# analog.net
KiCad netlist of a schematic drawn in EAGLE
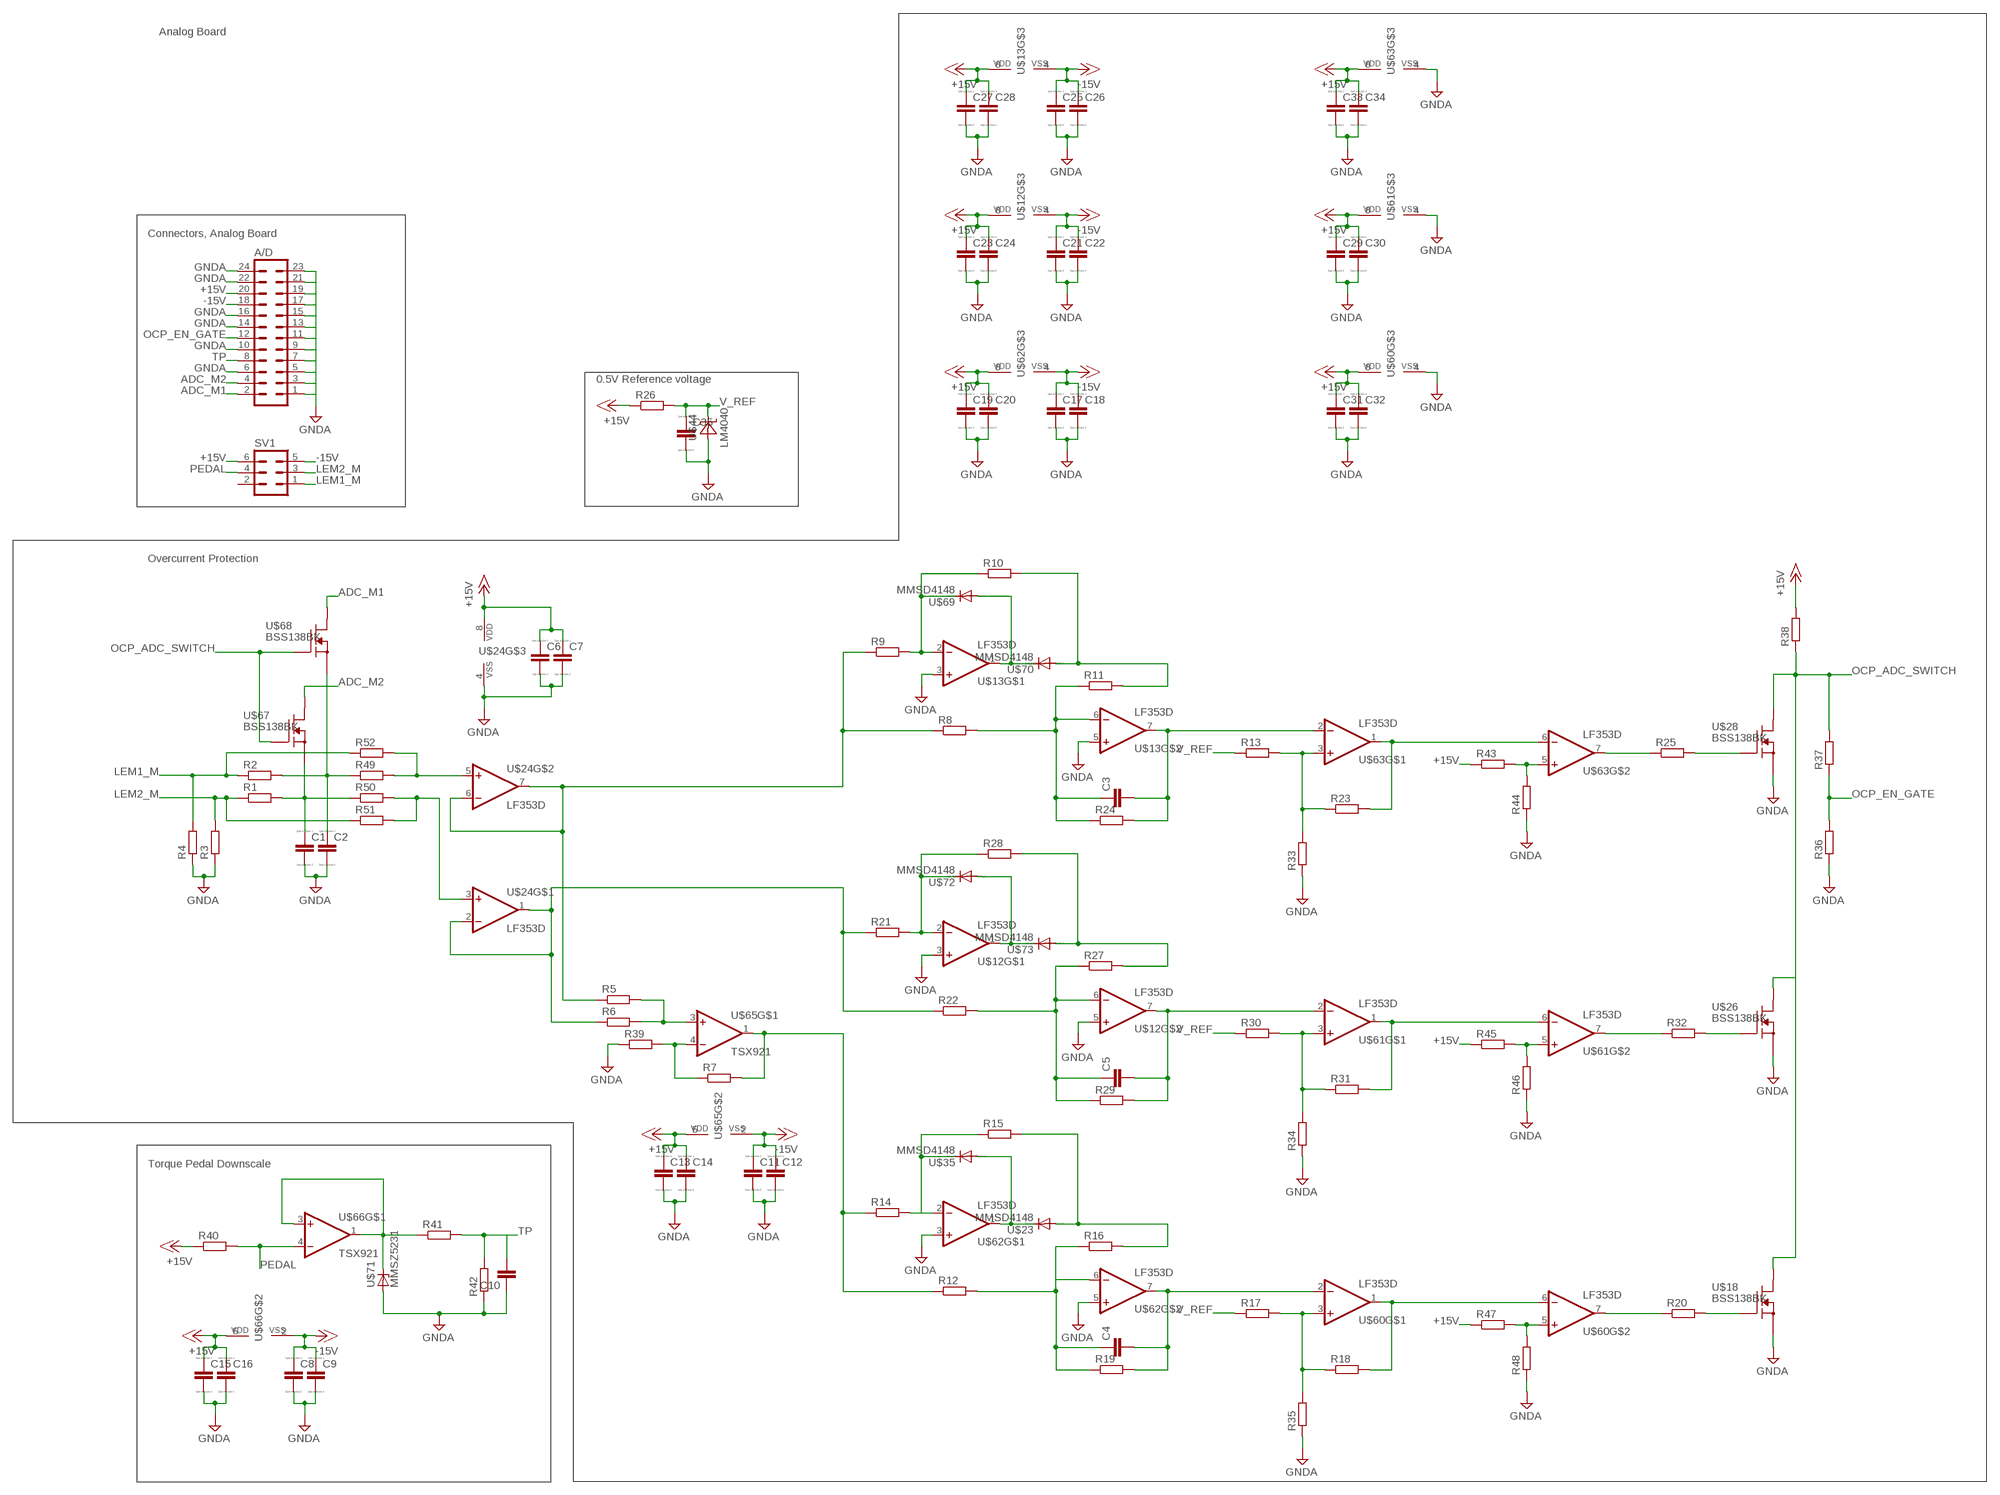
[diagram p0: schematic, sheet 1]

(export (version "E")
  (design (tool "Eeschema 10.0.6"))
  (components
    (comp (ref "A/D")
      (value "MA12-2")
      (footprint "eagle-import:MA12-2")
      (libsource (lib "eagle-import") (part "MA12-2"))
    )
    (comp (ref "C1")
      (value "CC1206")
      (footprint "eagle-import:C1206")
      (libsource (lib "eagle-import") (part "CC1206"))
    )
    (comp (ref "C2")
      (value "CC1206")
      (footprint "eagle-import:C1206")
      (libsource (lib "eagle-import") (part "CC1206"))
    )
    (comp (ref "C3")
      (value "C-EUC0805")
      (footprint "eagle-import:C0805")
      (libsource (lib "eagle-import") (part "C-EUC0805"))
    )
    (comp (ref "C4")
      (value "C-EUC0805")
      (footprint "eagle-import:C0805")
      (libsource (lib "eagle-import") (part "C-EUC0805"))
    )
    (comp (ref "C5")
      (value "C-EUC0805")
      (footprint "eagle-import:C0805")
      (libsource (lib "eagle-import") (part "C-EUC0805"))
    )
    (comp (ref "C6")
      (value "CC1206")
      (footprint "eagle-import:C1206")
      (libsource (lib "eagle-import") (part "CC1206"))
    )
    (comp (ref "C7")
      (value "CC1206")
      (footprint "eagle-import:C1206")
      (libsource (lib "eagle-import") (part "CC1206"))
    )
    (comp (ref "C8")
      (value "CC1206")
      (footprint "eagle-import:C1206")
      (libsource (lib "eagle-import") (part "CC1206"))
    )
    (comp (ref "C9")
      (value "CC1206")
      (footprint "eagle-import:C1206")
      (libsource (lib "eagle-import") (part "CC1206"))
    )
    (comp (ref "C10")
      (value "C-EUC0805")
      (footprint "eagle-import:C0805")
      (libsource (lib "eagle-import") (part "C-EUC0805"))
    )
    (comp (ref "C11")
      (value "CC1206")
      (footprint "eagle-import:C1206")
      (libsource (lib "eagle-import") (part "CC1206"))
    )
    (comp (ref "C12")
      (value "CC1206")
      (footprint "eagle-import:C1206")
      (libsource (lib "eagle-import") (part "CC1206"))
    )
    (comp (ref "C13")
      (value "CC1206")
      (footprint "eagle-import:C1206")
      (libsource (lib "eagle-import") (part "CC1206"))
    )
    (comp (ref "C14")
      (value "CC1206")
      (footprint "eagle-import:C1206")
      (libsource (lib "eagle-import") (part "CC1206"))
    )
    (comp (ref "C15")
      (value "CC1206")
      (footprint "eagle-import:C1206")
      (libsource (lib "eagle-import") (part "CC1206"))
    )
    (comp (ref "C16")
      (value "CC1206")
      (footprint "eagle-import:C1206")
      (libsource (lib "eagle-import") (part "CC1206"))
    )
    (comp (ref "C17")
      (value "CC1206")
      (footprint "eagle-import:C1206")
      (libsource (lib "eagle-import") (part "CC1206"))
    )
    (comp (ref "C18")
      (value "CC1206")
      (footprint "eagle-import:C1206")
      (libsource (lib "eagle-import") (part "CC1206"))
    )
    (comp (ref "C19")
      (value "CC1206")
      (footprint "eagle-import:C1206")
      (libsource (lib "eagle-import") (part "CC1206"))
    )
    (comp (ref "C20")
      (value "CC1206")
      (footprint "eagle-import:C1206")
      (libsource (lib "eagle-import") (part "CC1206"))
    )
    (comp (ref "C21")
      (value "CC1206")
      (footprint "eagle-import:C1206")
      (libsource (lib "eagle-import") (part "CC1206"))
    )
    (comp (ref "C22")
      (value "CC1206")
      (footprint "eagle-import:C1206")
      (libsource (lib "eagle-import") (part "CC1206"))
    )
    (comp (ref "C23")
      (value "CC1206")
      (footprint "eagle-import:C1206")
      (libsource (lib "eagle-import") (part "CC1206"))
    )
    (comp (ref "C24")
      (value "CC1206")
      (footprint "eagle-import:C1206")
      (libsource (lib "eagle-import") (part "CC1206"))
    )
    (comp (ref "C25")
      (value "CC1206")
      (footprint "eagle-import:C1206")
      (libsource (lib "eagle-import") (part "CC1206"))
    )
    (comp (ref "C26")
      (value "CC1206")
      (footprint "eagle-import:C1206")
      (libsource (lib "eagle-import") (part "CC1206"))
    )
    (comp (ref "C27")
      (value "CC1206")
      (footprint "eagle-import:C1206")
      (libsource (lib "eagle-import") (part "CC1206"))
    )
    (comp (ref "C28")
      (value "CC1206")
      (footprint "eagle-import:C1206")
      (libsource (lib "eagle-import") (part "CC1206"))
    )
    (comp (ref "C29")
      (value "CC1206")
      (footprint "eagle-import:C1206")
      (libsource (lib "eagle-import") (part "CC1206"))
    )
    (comp (ref "C30")
      (value "CC1206")
      (footprint "eagle-import:C1206")
      (libsource (lib "eagle-import") (part "CC1206"))
    )
    (comp (ref "C31")
      (value "CC1206")
      (footprint "eagle-import:C1206")
      (libsource (lib "eagle-import") (part "CC1206"))
    )
    (comp (ref "C32")
      (value "CC1206")
      (footprint "eagle-import:C1206")
      (libsource (lib "eagle-import") (part "CC1206"))
    )
    (comp (ref "C33")
      (value "CC1206")
      (footprint "eagle-import:C1206")
      (libsource (lib "eagle-import") (part "CC1206"))
    )
    (comp (ref "C34")
      (value "CC1206")
      (footprint "eagle-import:C1206")
      (libsource (lib "eagle-import") (part "CC1206"))
    )
    (comp (ref "C35")
      (value "CC1206")
      (footprint "eagle-import:C1206")
      (libsource (lib "eagle-import") (part "CC1206"))
    )
    (comp (ref "R1")
      (value "R-EU_M0805")
      (footprint "eagle-import:M0805")
      (libsource (lib "eagle-import") (part "R-EU_M0805"))
    )
    (comp (ref "R2")
      (value "R-EU_M0805")
      (footprint "eagle-import:M0805")
      (libsource (lib "eagle-import") (part "R-EU_M0805"))
    )
    (comp (ref "R3")
      (value "R-EU_M0805")
      (footprint "eagle-import:M0805")
      (libsource (lib "eagle-import") (part "R-EU_M0805"))
    )
    (comp (ref "R4")
      (value "R-EU_M0805")
      (footprint "eagle-import:M0805")
      (libsource (lib "eagle-import") (part "R-EU_M0805"))
    )
    (comp (ref "R5")
      (value "R-EU_M0805")
      (footprint "eagle-import:M0805")
      (libsource (lib "eagle-import") (part "R-EU_M0805"))
    )
    (comp (ref "R6")
      (value "R-EU_M0805")
      (footprint "eagle-import:M0805")
      (libsource (lib "eagle-import") (part "R-EU_M0805"))
    )
    (comp (ref "R7")
      (value "R-EU_M0805")
      (footprint "eagle-import:M0805")
      (libsource (lib "eagle-import") (part "R-EU_M0805"))
    )
    (comp (ref "R8")
      (value "R-EU_M0805")
      (footprint "eagle-import:M0805")
      (libsource (lib "eagle-import") (part "R-EU_M0805"))
    )
    (comp (ref "R9")
      (value "R-EU_M0805")
      (footprint "eagle-import:M0805")
      (libsource (lib "eagle-import") (part "R-EU_M0805"))
    )
    (comp (ref "R10")
      (value "R-EU_M0805")
      (footprint "eagle-import:M0805")
      (libsource (lib "eagle-import") (part "R-EU_M0805"))
    )
    (comp (ref "R11")
      (value "R-EU_M0805")
      (footprint "eagle-import:M0805")
      (libsource (lib "eagle-import") (part "R-EU_M0805"))
    )
    (comp (ref "R12")
      (value "R-EU_M0805")
      (footprint "eagle-import:M0805")
      (libsource (lib "eagle-import") (part "R-EU_M0805"))
    )
    (comp (ref "R13")
      (value "R-EU_M0805")
      (footprint "eagle-import:M0805")
      (libsource (lib "eagle-import") (part "R-EU_M0805"))
    )
    (comp (ref "R14")
      (value "R-EU_M0805")
      (footprint "eagle-import:M0805")
      (libsource (lib "eagle-import") (part "R-EU_M0805"))
    )
    (comp (ref "R15")
      (value "R-EU_M0805")
      (footprint "eagle-import:M0805")
      (libsource (lib "eagle-import") (part "R-EU_M0805"))
    )
    (comp (ref "R16")
      (value "R-EU_M0805")
      (footprint "eagle-import:M0805")
      (libsource (lib "eagle-import") (part "R-EU_M0805"))
    )
    (comp (ref "R17")
      (value "R-EU_M0805")
      (footprint "eagle-import:M0805")
      (libsource (lib "eagle-import") (part "R-EU_M0805"))
    )
    (comp (ref "R18")
      (value "R-EU_M0805")
      (footprint "eagle-import:M0805")
      (libsource (lib "eagle-import") (part "R-EU_M0805"))
    )
    (comp (ref "R19")
      (value "R-EU_M0805")
      (footprint "eagle-import:M0805")
      (libsource (lib "eagle-import") (part "R-EU_M0805"))
    )
    (comp (ref "R20")
      (value "R-EU_M0805")
      (footprint "eagle-import:M0805")
      (libsource (lib "eagle-import") (part "R-EU_M0805"))
    )
    (comp (ref "R21")
      (value "R-EU_M0805")
      (footprint "eagle-import:M0805")
      (libsource (lib "eagle-import") (part "R-EU_M0805"))
    )
    (comp (ref "R22")
      (value "R-EU_M0805")
      (footprint "eagle-import:M0805")
      (libsource (lib "eagle-import") (part "R-EU_M0805"))
    )
    (comp (ref "R23")
      (value "R-EU_M0805")
      (footprint "eagle-import:M0805")
      (libsource (lib "eagle-import") (part "R-EU_M0805"))
    )
    (comp (ref "R24")
      (value "R-EU_M0805")
      (footprint "eagle-import:M0805")
      (libsource (lib "eagle-import") (part "R-EU_M0805"))
    )
    (comp (ref "R25")
      (value "R-EU_M0805")
      (footprint "eagle-import:M0805")
      (libsource (lib "eagle-import") (part "R-EU_M0805"))
    )
    (comp (ref "R26")
      (value "R-EU_M0805")
      (footprint "eagle-import:M0805")
      (libsource (lib "eagle-import") (part "R-EU_M0805"))
    )
    (comp (ref "R27")
      (value "R-EU_M0805")
      (footprint "eagle-import:M0805")
      (libsource (lib "eagle-import") (part "R-EU_M0805"))
    )
    (comp (ref "R28")
      (value "R-EU_M0805")
      (footprint "eagle-import:M0805")
      (libsource (lib "eagle-import") (part "R-EU_M0805"))
    )
    (comp (ref "R29")
      (value "R-EU_M0805")
      (footprint "eagle-import:M0805")
      (libsource (lib "eagle-import") (part "R-EU_M0805"))
    )
    (comp (ref "R30")
      (value "R-EU_M0805")
      (footprint "eagle-import:M0805")
      (libsource (lib "eagle-import") (part "R-EU_M0805"))
    )
    (comp (ref "R31")
      (value "R-EU_M0805")
      (footprint "eagle-import:M0805")
      (libsource (lib "eagle-import") (part "R-EU_M0805"))
    )
    (comp (ref "R32")
      (value "R-EU_M0805")
      (footprint "eagle-import:M0805")
      (libsource (lib "eagle-import") (part "R-EU_M0805"))
    )
    (comp (ref "R33")
      (value "R-EU_M0805")
      (footprint "eagle-import:M0805")
      (libsource (lib "eagle-import") (part "R-EU_M0805"))
    )
    (comp (ref "R34")
      (value "R-EU_M0805")
      (footprint "eagle-import:M0805")
      (libsource (lib "eagle-import") (part "R-EU_M0805"))
    )
    (comp (ref "R35")
      (value "R-EU_M0805")
      (footprint "eagle-import:M0805")
      (libsource (lib "eagle-import") (part "R-EU_M0805"))
    )
    (comp (ref "R36")
      (value "R-EU_M0805")
      (footprint "eagle-import:M0805")
      (libsource (lib "eagle-import") (part "R-EU_M0805"))
    )
    (comp (ref "R37")
      (value "R-EU_M0805")
      (footprint "eagle-import:M0805")
      (libsource (lib "eagle-import") (part "R-EU_M0805"))
    )
    (comp (ref "R38")
      (value "R-EU_M0805")
      (footprint "eagle-import:M0805")
      (libsource (lib "eagle-import") (part "R-EU_M0805"))
    )
    (comp (ref "R39")
      (value "R-EU_M0805")
      (footprint "eagle-import:M0805")
      (libsource (lib "eagle-import") (part "R-EU_M0805"))
    )
    (comp (ref "R40")
      (value "R-EU_M0805")
      (footprint "eagle-import:M0805")
      (libsource (lib "eagle-import") (part "R-EU_M0805"))
    )
    (comp (ref "R41")
      (value "R-EU_M0805")
      (footprint "eagle-import:M0805")
      (libsource (lib "eagle-import") (part "R-EU_M0805"))
    )
    (comp (ref "R42")
      (value "R-EU_M0805")
      (footprint "eagle-import:M0805")
      (libsource (lib "eagle-import") (part "R-EU_M0805"))
    )
    (comp (ref "R43")
      (value "R-EU_M0805")
      (footprint "eagle-import:M0805")
      (libsource (lib "eagle-import") (part "R-EU_M0805"))
    )
    (comp (ref "R44")
      (value "R-EU_M0805")
      (footprint "eagle-import:M0805")
      (libsource (lib "eagle-import") (part "R-EU_M0805"))
    )
    (comp (ref "R45")
      (value "R-EU_M0805")
      (footprint "eagle-import:M0805")
      (libsource (lib "eagle-import") (part "R-EU_M0805"))
    )
    (comp (ref "R46")
      (value "R-EU_M0805")
      (footprint "eagle-import:M0805")
      (libsource (lib "eagle-import") (part "R-EU_M0805"))
    )
    (comp (ref "R47")
      (value "R-EU_M0805")
      (footprint "eagle-import:M0805")
      (libsource (lib "eagle-import") (part "R-EU_M0805"))
    )
    (comp (ref "R48")
      (value "R-EU_M0805")
      (footprint "eagle-import:M0805")
      (libsource (lib "eagle-import") (part "R-EU_M0805"))
    )
    (comp (ref "R49")
      (value "R-EU_M0805")
      (footprint "eagle-import:M0805")
      (libsource (lib "eagle-import") (part "R-EU_M0805"))
    )
    (comp (ref "R50")
      (value "R-EU_M0805")
      (footprint "eagle-import:M0805")
      (libsource (lib "eagle-import") (part "R-EU_M0805"))
    )
    (comp (ref "R51")
      (value "R-EU_M0805")
      (footprint "eagle-import:M0805")
      (libsource (lib "eagle-import") (part "R-EU_M0805"))
    )
    (comp (ref "R52")
      (value "R-EU_M0805")
      (footprint "eagle-import:M0805")
      (libsource (lib "eagle-import") (part "R-EU_M0805"))
    )
    (comp (ref "SV1")
      (value "MA03-2")
      (footprint "eagle-import:MA03-2")
      (libsource (lib "eagle-import") (part "MA03-2"))
    )
    (comp (ref "U$12")
      (value "LF353D")
      (footprint "eagle-import:SO08")
      (libsource (lib "eagle-import") (part "LF353D"))
    )
    (comp (ref "U$13")
      (value "LF353D")
      (footprint "eagle-import:SO08")
      (libsource (lib "eagle-import") (part "LF353D"))
    )
    (comp (ref "U$18")
      (value "BSS138BK")
      (footprint "eagle-import:SOT23")
      (libsource (lib "eagle-import") (part "BSS138BK"))
    )
    (comp (ref "U$23")
      (value "MMSD4148")
      (footprint "eagle-import:SOD123")
      (libsource (lib "eagle-import") (part "MMSD4148"))
    )
    (comp (ref "U$24")
      (value "LF353D")
      (footprint "eagle-import:SO08")
      (libsource (lib "eagle-import") (part "LF353D"))
    )
    (comp (ref "U$26")
      (value "BSS138BK")
      (footprint "eagle-import:SOT23")
      (libsource (lib "eagle-import") (part "BSS138BK"))
    )
    (comp (ref "U$28")
      (value "BSS138BK")
      (footprint "eagle-import:SOT23")
      (libsource (lib "eagle-import") (part "BSS138BK"))
    )
    (comp (ref "U$35")
      (value "MMSD4148")
      (footprint "eagle-import:SOD123")
      (libsource (lib "eagle-import") (part "MMSD4148"))
    )
    (comp (ref "U$44")
      (value "LM4040")
      (footprint "eagle-import:SOT23")
      (libsource (lib "eagle-import") (part "LM4040"))
    )
    (comp (ref "U$60")
      (value "LF353D")
      (footprint "eagle-import:SO08")
      (libsource (lib "eagle-import") (part "LF353D"))
    )
    (comp (ref "U$61")
      (value "LF353D")
      (footprint "eagle-import:SO08")
      (libsource (lib "eagle-import") (part "LF353D"))
    )
    (comp (ref "U$62")
      (value "LF353D")
      (footprint "eagle-import:SO08")
      (libsource (lib "eagle-import") (part "LF353D"))
    )
    (comp (ref "U$63")
      (value "LF353D")
      (footprint "eagle-import:SO08")
      (libsource (lib "eagle-import") (part "LF353D"))
    )
    (comp (ref "U$65")
      (value "TSX921")
      (footprint "eagle-import:SOT23-5")
      (libsource (lib "eagle-import") (part "TSX921"))
    )
    (comp (ref "U$66")
      (value "TSX921")
      (footprint "eagle-import:SOT23-5")
      (libsource (lib "eagle-import") (part "TSX921"))
    )
    (comp (ref "U$67")
      (value "BSS138BK")
      (footprint "eagle-import:SOT23")
      (libsource (lib "eagle-import") (part "BSS138BK"))
    )
    (comp (ref "U$68")
      (value "BSS138BK")
      (footprint "eagle-import:SOT23")
      (libsource (lib "eagle-import") (part "BSS138BK"))
    )
    (comp (ref "U$69")
      (value "MMSD4148")
      (footprint "eagle-import:SOD123")
      (libsource (lib "eagle-import") (part "MMSD4148"))
    )
    (comp (ref "U$70")
      (value "MMSD4148")
      (footprint "eagle-import:SOD123")
      (libsource (lib "eagle-import") (part "MMSD4148"))
    )
    (comp (ref "U$71")
      (value "MMSZ5231")
      (footprint "eagle-import:SOD123")
      (libsource (lib "eagle-import") (part "MMSZ5231"))
    )
    (comp (ref "U$72")
      (value "MMSD4148")
      (footprint "eagle-import:SOD123")
      (libsource (lib "eagle-import") (part "MMSD4148"))
    )
    (comp (ref "U$73")
      (value "MMSD4148")
      (footprint "eagle-import:SOD123")
      (libsource (lib "eagle-import") (part "MMSD4148"))
    )
  )
  (nets
    (net (code "1") (name "+15V") (class "Default")
      (node (ref "A/D") (pin "20") (pinfunction "20_20") (pintype "passive"))
      (node (ref "C13") (pin "1") (pinfunction "1_1") (pintype "passive"))
      (node (ref "C14") (pin "1") (pinfunction "1_1") (pintype "passive"))
      (node (ref "C15") (pin "1") (pinfunction "1_1") (pintype "passive"))
      (node (ref "C16") (pin "1") (pinfunction "1_1") (pintype "passive"))
      (node (ref "C19") (pin "1") (pinfunction "1_1") (pintype "passive"))
      (node (ref "C20") (pin "1") (pinfunction "1_1") (pintype "passive"))
      (node (ref "C23") (pin "1") (pinfunction "1_1") (pintype "passive"))
      (node (ref "C24") (pin "1") (pinfunction "1_1") (pintype "passive"))
      (node (ref "C27") (pin "1") (pinfunction "1_1") (pintype "passive"))
      (node (ref "C28") (pin "1") (pinfunction "1_1") (pintype "passive"))
      (node (ref "C29") (pin "1") (pinfunction "1_1") (pintype "passive"))
      (node (ref "C30") (pin "1") (pinfunction "1_1") (pintype "passive"))
      (node (ref "C31") (pin "1") (pinfunction "1_1") (pintype "passive"))
      (node (ref "C32") (pin "1") (pinfunction "1_1") (pintype "passive"))
      (node (ref "C33") (pin "1") (pinfunction "1_1") (pintype "passive"))
      (node (ref "C34") (pin "1") (pinfunction "1_1") (pintype "passive"))
      (node (ref "C6") (pin "1") (pinfunction "1_1") (pintype "passive"))
      (node (ref "C7") (pin "1") (pinfunction "1_1") (pintype "passive"))
      (node (ref "R26") (pin "1") (pinfunction "1_1") (pintype "passive"))
      (node (ref "R38") (pin "2") (pinfunction "2_2") (pintype "passive"))
      (node (ref "R40") (pin "1") (pinfunction "1_1") (pintype "passive"))
      (node (ref "R43") (pin "1") (pinfunction "1_1") (pintype "passive"))
      (node (ref "R45") (pin "1") (pinfunction "1_1") (pintype "passive"))
      (node (ref "R47") (pin "1") (pinfunction "1_1") (pintype "passive"))
      (node (ref "SV1") (pin "6") (pinfunction "6_6") (pintype "passive"))
      (node (ref "U$12") (pin "8") (pinfunction "VDD_8") (pintype "power_in"))
      (node (ref "U$13") (pin "8") (pinfunction "VDD_8") (pintype "power_in"))
      (node (ref "U$24") (pin "8") (pinfunction "VDD_8") (pintype "power_in"))
      (node (ref "U$60") (pin "8") (pinfunction "VDD_8") (pintype "power_in"))
      (node (ref "U$61") (pin "8") (pinfunction "VDD_8") (pintype "power_in"))
      (node (ref "U$62") (pin "8") (pinfunction "VDD_8") (pintype "power_in"))
      (node (ref "U$63") (pin "8") (pinfunction "VDD_8") (pintype "power_in"))
      (node (ref "U$65") (pin "5") (pinfunction "VDD_5") (pintype "power_in"))
      (node (ref "U$66") (pin "5") (pinfunction "VDD_5") (pintype "power_in"))
    )
    (net (code "2") (name "-15V") (class "Default")
      (node (ref "A/D") (pin "18") (pinfunction "18_18") (pintype "passive"))
      (node (ref "C11") (pin "1") (pinfunction "1_1") (pintype "passive"))
      (node (ref "C12") (pin "1") (pinfunction "1_1") (pintype "passive"))
      (node (ref "C17") (pin "1") (pinfunction "1_1") (pintype "passive"))
      (node (ref "C18") (pin "1") (pinfunction "1_1") (pintype "passive"))
      (node (ref "C21") (pin "1") (pinfunction "1_1") (pintype "passive"))
      (node (ref "C22") (pin "1") (pinfunction "1_1") (pintype "passive"))
      (node (ref "C25") (pin "1") (pinfunction "1_1") (pintype "passive"))
      (node (ref "C26") (pin "1") (pinfunction "1_1") (pintype "passive"))
      (node (ref "C8") (pin "1") (pinfunction "1_1") (pintype "passive"))
      (node (ref "C9") (pin "1") (pinfunction "1_1") (pintype "passive"))
      (node (ref "SV1") (pin "5") (pinfunction "5_5") (pintype "passive"))
      (node (ref "U$12") (pin "4") (pinfunction "VSS_4") (pintype "power_in"))
      (node (ref "U$13") (pin "4") (pinfunction "VSS_4") (pintype "power_in"))
      (node (ref "U$62") (pin "4") (pinfunction "VSS_4") (pintype "power_in"))
      (node (ref "U$65") (pin "2") (pinfunction "VSS_2") (pintype "power_in"))
      (node (ref "U$66") (pin "2") (pinfunction "VSS_2") (pintype "power_in"))
    )
    (net (code "3") (name "/ADC_M1") (class "Default")
      (node (ref "A/D") (pin "2") (pinfunction "2_2") (pintype "passive"))
      (node (ref "U$68") (pin "3") (pinfunction "D_3") (pintype "passive"))
    )
    (net (code "4") (name "/ADC_M2") (class "Default")
      (node (ref "A/D") (pin "4") (pinfunction "4_4") (pintype "passive"))
      (node (ref "U$67") (pin "3") (pinfunction "D_3") (pintype "passive"))
    )
    (net (code "5") (name "/LEM1_M") (class "Default")
      (node (ref "R2") (pin "1") (pinfunction "1_1") (pintype "passive"))
      (node (ref "R4") (pin "2") (pinfunction "2_2") (pintype "passive"))
      (node (ref "R52") (pin "1") (pinfunction "1_1") (pintype "passive"))
      (node (ref "SV1") (pin "1") (pinfunction "1_1") (pintype "passive"))
    )
    (net (code "6") (name "/LEM2_M") (class "Default")
      (node (ref "R1") (pin "1") (pinfunction "1_1") (pintype "passive"))
      (node (ref "R3") (pin "2") (pinfunction "2_2") (pintype "passive"))
      (node (ref "R51") (pin "1") (pinfunction "1_1") (pintype "passive"))
      (node (ref "SV1") (pin "3") (pinfunction "3_3") (pintype "passive"))
    )
    (net (code "7") (name "/OCP_ADC_SWITCH") (class "Default")
      (node (ref "R37") (pin "2") (pinfunction "2_2") (pintype "passive"))
      (node (ref "R38") (pin "1") (pinfunction "1_1") (pintype "passive"))
      (node (ref "U$18") (pin "3") (pinfunction "D_3") (pintype "passive"))
      (node (ref "U$26") (pin "3") (pinfunction "D_3") (pintype "passive"))
      (node (ref "U$28") (pin "3") (pinfunction "D_3") (pintype "passive"))
      (node (ref "U$67") (pin "1") (pinfunction "G_1") (pintype "passive"))
      (node (ref "U$68") (pin "1") (pinfunction "G_1") (pintype "passive"))
    )
    (net (code "8") (name "/OCP_EN_GATE") (class "Default")
      (node (ref "A/D") (pin "12") (pinfunction "12_12") (pintype "passive"))
      (node (ref "R36") (pin "2") (pinfunction "2_2") (pintype "passive"))
      (node (ref "R37") (pin "1") (pinfunction "1_1") (pintype "passive"))
    )
    (net (code "9") (name "/PEDAL") (class "Default")
      (node (ref "R40") (pin "2") (pinfunction "2_2") (pintype "passive"))
      (node (ref "SV1") (pin "4") (pinfunction "4_4") (pintype "passive"))
      (node (ref "U$66") (pin "4") (pinfunction "-IN_4") (pintype "input"))
    )
    (net (code "10") (name "/TP") (class "Default")
      (node (ref "A/D") (pin "8") (pinfunction "8_8") (pintype "passive"))
      (node (ref "C10") (pin "2") (pinfunction "2_2") (pintype "passive"))
      (node (ref "R41") (pin "2") (pinfunction "2_2") (pintype "passive"))
      (node (ref "R42") (pin "2") (pinfunction "2_2") (pintype "passive"))
    )
    (net (code "11") (name "/V_REF") (class "Default")
      (node (ref "C35") (pin "1") (pinfunction "1_1") (pintype "passive"))
      (node (ref "R13") (pin "1") (pinfunction "1_1") (pintype "passive"))
      (node (ref "R17") (pin "1") (pinfunction "1_1") (pintype "passive"))
      (node (ref "R26") (pin "2") (pinfunction "2_2") (pintype "passive"))
      (node (ref "R30") (pin "1") (pinfunction "1_1") (pintype "passive"))
      (node (ref "U$44") (pin "2") (pinfunction "C_2") (pintype "passive"))
    )
    (net (code "12") (name "GNDA") (class "Default")
      (node (ref "A/D") (pin "1") (pinfunction "1_1") (pintype "passive"))
      (node (ref "A/D") (pin "10") (pinfunction "10_10") (pintype "passive"))
      (node (ref "A/D") (pin "11") (pinfunction "11_11") (pintype "passive"))
      (node (ref "A/D") (pin "13") (pinfunction "13_13") (pintype "passive"))
      (node (ref "A/D") (pin "14") (pinfunction "14_14") (pintype "passive"))
      (node (ref "A/D") (pin "15") (pinfunction "15_15") (pintype "passive"))
      (node (ref "A/D") (pin "16") (pinfunction "16_16") (pintype "passive"))
      (node (ref "A/D") (pin "22") (pinfunction "22_22") (pintype "passive"))
      (node (ref "A/D") (pin "23") (pinfunction "23_23") (pintype "passive"))
      (node (ref "A/D") (pin "24") (pinfunction "24_24") (pintype "passive"))
      (node (ref "A/D") (pin "3") (pinfunction "3_3") (pintype "passive"))
      (node (ref "A/D") (pin "5") (pinfunction "5_5") (pintype "passive"))
      (node (ref "A/D") (pin "6") (pinfunction "6_6") (pintype "passive"))
      (node (ref "A/D") (pin "7") (pinfunction "7_7") (pintype "passive"))
      (node (ref "A/D") (pin "9") (pinfunction "9_9") (pintype "passive"))
      (node (ref "C1") (pin "2") (pinfunction "2_2") (pintype "passive"))
      (node (ref "C10") (pin "1") (pinfunction "1_1") (pintype "passive"))
      (node (ref "C11") (pin "2") (pinfunction "2_2") (pintype "passive"))
      (node (ref "C12") (pin "2") (pinfunction "2_2") (pintype "passive"))
      (node (ref "C13") (pin "2") (pinfunction "2_2") (pintype "passive"))
      (node (ref "C14") (pin "2") (pinfunction "2_2") (pintype "passive"))
      (node (ref "C15") (pin "2") (pinfunction "2_2") (pintype "passive"))
      (node (ref "C16") (pin "2") (pinfunction "2_2") (pintype "passive"))
      (node (ref "C17") (pin "2") (pinfunction "2_2") (pintype "passive"))
      (node (ref "C18") (pin "2") (pinfunction "2_2") (pintype "passive"))
      (node (ref "C19") (pin "2") (pinfunction "2_2") (pintype "passive"))
      (node (ref "C2") (pin "2") (pinfunction "2_2") (pintype "passive"))
      (node (ref "C20") (pin "2") (pinfunction "2_2") (pintype "passive"))
      (node (ref "C21") (pin "2") (pinfunction "2_2") (pintype "passive"))
      (node (ref "C22") (pin "2") (pinfunction "2_2") (pintype "passive"))
      (node (ref "C23") (pin "2") (pinfunction "2_2") (pintype "passive"))
      (node (ref "C24") (pin "2") (pinfunction "2_2") (pintype "passive"))
      (node (ref "C25") (pin "2") (pinfunction "2_2") (pintype "passive"))
      (node (ref "C26") (pin "2") (pinfunction "2_2") (pintype "passive"))
      (node (ref "C27") (pin "2") (pinfunction "2_2") (pintype "passive"))
      (node (ref "C28") (pin "2") (pinfunction "2_2") (pintype "passive"))
      (node (ref "C29") (pin "2") (pinfunction "2_2") (pintype "passive"))
      (node (ref "C30") (pin "2") (pinfunction "2_2") (pintype "passive"))
      (node (ref "C31") (pin "2") (pinfunction "2_2") (pintype "passive"))
      (node (ref "C32") (pin "2") (pinfunction "2_2") (pintype "passive"))
      (node (ref "C33") (pin "2") (pinfunction "2_2") (pintype "passive"))
      (node (ref "C34") (pin "2") (pinfunction "2_2") (pintype "passive"))
      (node (ref "C35") (pin "2") (pinfunction "2_2") (pintype "passive"))
      (node (ref "C6") (pin "2") (pinfunction "2_2") (pintype "passive"))
      (node (ref "C7") (pin "2") (pinfunction "2_2") (pintype "passive"))
      (node (ref "C8") (pin "2") (pinfunction "2_2") (pintype "passive"))
      (node (ref "C9") (pin "2") (pinfunction "2_2") (pintype "passive"))
      (node (ref "R3") (pin "1") (pinfunction "1_1") (pintype "passive"))
      (node (ref "R33") (pin "1") (pinfunction "1_1") (pintype "passive"))
      (node (ref "R34") (pin "1") (pinfunction "1_1") (pintype "passive"))
      (node (ref "R35") (pin "1") (pinfunction "1_1") (pintype "passive"))
      (node (ref "R36") (pin "1") (pinfunction "1_1") (pintype "passive"))
      (node (ref "R39") (pin "1") (pinfunction "1_1") (pintype "passive"))
      (node (ref "R4") (pin "1") (pinfunction "1_1") (pintype "passive"))
      (node (ref "R42") (pin "1") (pinfunction "1_1") (pintype "passive"))
      (node (ref "R44") (pin "1") (pinfunction "1_1") (pintype "passive"))
      (node (ref "R46") (pin "1") (pinfunction "1_1") (pintype "passive"))
      (node (ref "R48") (pin "1") (pinfunction "1_1") (pintype "passive"))
      (node (ref "U$12") (pin "3") (pinfunction "+IN_3") (pintype "input"))
      (node (ref "U$12") (pin "5") (pinfunction "+IN_5") (pintype "input"))
      (node (ref "U$13") (pin "3") (pinfunction "+IN_3") (pintype "input"))
      (node (ref "U$13") (pin "5") (pinfunction "+IN_5") (pintype "input"))
      (node (ref "U$18") (pin "2") (pinfunction "S_2") (pintype "passive"))
      (node (ref "U$24") (pin "4") (pinfunction "VSS_4") (pintype "power_in"))
      (node (ref "U$26") (pin "2") (pinfunction "S_2") (pintype "passive"))
      (node (ref "U$28") (pin "2") (pinfunction "S_2") (pintype "passive"))
      (node (ref "U$44") (pin "1") (pinfunction "A_1") (pintype "passive"))
      (node (ref "U$60") (pin "4") (pinfunction "VSS_4") (pintype "power_in"))
      (node (ref "U$61") (pin "4") (pinfunction "VSS_4") (pintype "power_in"))
      (node (ref "U$62") (pin "3") (pinfunction "+IN_3") (pintype "input"))
      (node (ref "U$62") (pin "5") (pinfunction "+IN_5") (pintype "input"))
      (node (ref "U$63") (pin "4") (pinfunction "VSS_4") (pintype "power_in"))
      (node (ref "U$71") (pin "A") (pinfunction "A_A") (pintype "passive"))
    )
    (net (code "13") (name "Net-(R10-Pad2)") (class "Default")
      (node (ref "R10") (pin "2") (pinfunction "2_2") (pintype "passive"))
      (node (ref "R11") (pin "2") (pinfunction "2_2") (pintype "passive"))
      (node (ref "U$70") (pin "A") (pinfunction "A_A") (pintype "passive"))
    )
    (net (code "14") (name "Net-(R15-Pad2)") (class "Default")
      (node (ref "R15") (pin "2") (pinfunction "2_2") (pintype "passive"))
      (node (ref "R16") (pin "2") (pinfunction "2_2") (pintype "passive"))
      (node (ref "U$23") (pin "A") (pinfunction "A_A") (pintype "passive"))
    )
    (net (code "15") (name "Net-(R27-Pad2)") (class "Default")
      (node (ref "R27") (pin "2") (pinfunction "2_2") (pintype "passive"))
      (node (ref "R28") (pin "2") (pinfunction "2_2") (pintype "passive"))
      (node (ref "U$73") (pin "A") (pinfunction "A_A") (pintype "passive"))
    )
    (net (code "16") (name "Net-(U$12A--IN)") (class "Default")
      (node (ref "R21") (pin "2") (pinfunction "2_2") (pintype "passive"))
      (node (ref "R28") (pin "1") (pinfunction "1_1") (pintype "passive"))
      (node (ref "U$12") (pin "2") (pinfunction "-IN_2") (pintype "input"))
      (node (ref "U$72") (pin "C") (pinfunction "C_C") (pintype "passive"))
    )
    (net (code "17") (name "Net-(U$12A-OUT)") (class "Default")
      (node (ref "U$12") (pin "1") (pinfunction "OUT_1") (pintype "output"))
      (node (ref "U$72") (pin "A") (pinfunction "A_A") (pintype "passive"))
      (node (ref "U$73") (pin "C") (pinfunction "C_C") (pintype "passive"))
    )
    (net (code "18") (name "Net-(U$12B--IN)") (class "Default")
      (node (ref "C5") (pin "1") (pinfunction "1_1") (pintype "passive"))
      (node (ref "R22") (pin "2") (pinfunction "2_2") (pintype "passive"))
      (node (ref "R27") (pin "1") (pinfunction "1_1") (pintype "passive"))
      (node (ref "R29") (pin "1") (pinfunction "1_1") (pintype "passive"))
      (node (ref "U$12") (pin "6") (pinfunction "-IN_6") (pintype "input"))
    )
    (net (code "19") (name "Net-(U$12B-OUT)") (class "Default")
      (node (ref "C5") (pin "2") (pinfunction "2_2") (pintype "passive"))
      (node (ref "R29") (pin "2") (pinfunction "2_2") (pintype "passive"))
      (node (ref "U$12") (pin "7") (pinfunction "OUT_7") (pintype "output"))
      (node (ref "U$61") (pin "2") (pinfunction "-IN_2") (pintype "input"))
    )
    (net (code "20") (name "Net-(U$13A--IN)") (class "Default")
      (node (ref "R10") (pin "1") (pinfunction "1_1") (pintype "passive"))
      (node (ref "R9") (pin "2") (pinfunction "2_2") (pintype "passive"))
      (node (ref "U$13") (pin "2") (pinfunction "-IN_2") (pintype "input"))
      (node (ref "U$69") (pin "C") (pinfunction "C_C") (pintype "passive"))
    )
    (net (code "21") (name "Net-(U$13A-OUT)") (class "Default")
      (node (ref "U$13") (pin "1") (pinfunction "OUT_1") (pintype "output"))
      (node (ref "U$69") (pin "A") (pinfunction "A_A") (pintype "passive"))
      (node (ref "U$70") (pin "C") (pinfunction "C_C") (pintype "passive"))
    )
    (net (code "22") (name "Net-(U$13B--IN)") (class "Default")
      (node (ref "C3") (pin "1") (pinfunction "1_1") (pintype "passive"))
      (node (ref "R11") (pin "1") (pinfunction "1_1") (pintype "passive"))
      (node (ref "R24") (pin "1") (pinfunction "1_1") (pintype "passive"))
      (node (ref "R8") (pin "2") (pinfunction "2_2") (pintype "passive"))
      (node (ref "U$13") (pin "6") (pinfunction "-IN_6") (pintype "input"))
    )
    (net (code "23") (name "Net-(U$13B-OUT)") (class "Default")
      (node (ref "C3") (pin "2") (pinfunction "2_2") (pintype "passive"))
      (node (ref "R24") (pin "2") (pinfunction "2_2") (pintype "passive"))
      (node (ref "U$13") (pin "7") (pinfunction "OUT_7") (pintype "output"))
      (node (ref "U$63") (pin "2") (pinfunction "-IN_2") (pintype "input"))
    )
    (net (code "24") (name "Net-(U$18-G)") (class "Default")
      (node (ref "R20") (pin "2") (pinfunction "2_2") (pintype "passive"))
      (node (ref "U$18") (pin "1") (pinfunction "G_1") (pintype "passive"))
    )
    (net (code "25") (name "Net-(U$24A-+IN)") (class "Default")
      (node (ref "R50") (pin "2") (pinfunction "2_2") (pintype "passive"))
      (node (ref "R51") (pin "2") (pinfunction "2_2") (pintype "passive"))
      (node (ref "U$24") (pin "3") (pinfunction "+IN_3") (pintype "input"))
    )
    (net (code "26") (name "Net-(U$24A--IN)") (class "Default")
      (node (ref "R21") (pin "1") (pinfunction "1_1") (pintype "passive"))
      (node (ref "R22") (pin "1") (pinfunction "1_1") (pintype "passive"))
      (node (ref "R6") (pin "1") (pinfunction "1_1") (pintype "passive"))
      (node (ref "U$24") (pin "1") (pinfunction "OUT_1") (pintype "output"))
      (node (ref "U$24") (pin "2") (pinfunction "-IN_2") (pintype "input"))
    )
    (net (code "27") (name "Net-(U$24B-+IN)") (class "Default")
      (node (ref "R49") (pin "2") (pinfunction "2_2") (pintype "passive"))
      (node (ref "R52") (pin "2") (pinfunction "2_2") (pintype "passive"))
      (node (ref "U$24") (pin "5") (pinfunction "+IN_5") (pintype "input"))
    )
    (net (code "28") (name "Net-(U$24B--IN)") (class "Default")
      (node (ref "R5") (pin "1") (pinfunction "1_1") (pintype "passive"))
      (node (ref "R8") (pin "1") (pinfunction "1_1") (pintype "passive"))
      (node (ref "R9") (pin "1") (pinfunction "1_1") (pintype "passive"))
      (node (ref "U$24") (pin "6") (pinfunction "-IN_6") (pintype "input"))
      (node (ref "U$24") (pin "7") (pinfunction "OUT_7") (pintype "output"))
    )
    (net (code "29") (name "Net-(U$26-G)") (class "Default")
      (node (ref "R32") (pin "2") (pinfunction "2_2") (pintype "passive"))
      (node (ref "U$26") (pin "1") (pinfunction "G_1") (pintype "passive"))
    )
    (net (code "30") (name "Net-(U$28-G)") (class "Default")
      (node (ref "R25") (pin "2") (pinfunction "2_2") (pintype "passive"))
      (node (ref "U$28") (pin "1") (pinfunction "G_1") (pintype "passive"))
    )
    (net (code "31") (name "Net-(U$60A-+IN)") (class "Default")
      (node (ref "R17") (pin "2") (pinfunction "2_2") (pintype "passive"))
      (node (ref "R18") (pin "1") (pinfunction "1_1") (pintype "passive"))
      (node (ref "R35") (pin "2") (pinfunction "2_2") (pintype "passive"))
      (node (ref "U$60") (pin "3") (pinfunction "+IN_3") (pintype "input"))
    )
    (net (code "32") (name "Net-(U$60A--IN)") (class "Default")
      (node (ref "C4") (pin "2") (pinfunction "2_2") (pintype "passive"))
      (node (ref "R19") (pin "2") (pinfunction "2_2") (pintype "passive"))
      (node (ref "U$60") (pin "2") (pinfunction "-IN_2") (pintype "input"))
      (node (ref "U$62") (pin "7") (pinfunction "OUT_7") (pintype "output"))
    )
    (net (code "33") (name "Net-(U$60A-OUT)") (class "Default")
      (node (ref "R18") (pin "2") (pinfunction "2_2") (pintype "passive"))
      (node (ref "U$60") (pin "1") (pinfunction "OUT_1") (pintype "output"))
      (node (ref "U$60") (pin "6") (pinfunction "-IN_6") (pintype "input"))
    )
    (net (code "34") (name "Net-(U$60B-+IN)") (class "Default")
      (node (ref "R47") (pin "2") (pinfunction "2_2") (pintype "passive"))
      (node (ref "R48") (pin "2") (pinfunction "2_2") (pintype "passive"))
      (node (ref "U$60") (pin "5") (pinfunction "+IN_5") (pintype "input"))
    )
    (net (code "35") (name "Net-(U$60B-OUT)") (class "Default")
      (node (ref "R20") (pin "1") (pinfunction "1_1") (pintype "passive"))
      (node (ref "U$60") (pin "7") (pinfunction "OUT_7") (pintype "output"))
    )
    (net (code "36") (name "Net-(U$61A-+IN)") (class "Default")
      (node (ref "R30") (pin "2") (pinfunction "2_2") (pintype "passive"))
      (node (ref "R31") (pin "1") (pinfunction "1_1") (pintype "passive"))
      (node (ref "R34") (pin "2") (pinfunction "2_2") (pintype "passive"))
      (node (ref "U$61") (pin "3") (pinfunction "+IN_3") (pintype "input"))
    )
    (net (code "37") (name "Net-(U$61A-OUT)") (class "Default")
      (node (ref "R31") (pin "2") (pinfunction "2_2") (pintype "passive"))
      (node (ref "U$61") (pin "1") (pinfunction "OUT_1") (pintype "output"))
      (node (ref "U$61") (pin "6") (pinfunction "-IN_6") (pintype "input"))
    )
    (net (code "38") (name "Net-(U$61B-+IN)") (class "Default")
      (node (ref "R45") (pin "2") (pinfunction "2_2") (pintype "passive"))
      (node (ref "R46") (pin "2") (pinfunction "2_2") (pintype "passive"))
      (node (ref "U$61") (pin "5") (pinfunction "+IN_5") (pintype "input"))
    )
    (net (code "39") (name "Net-(U$61B-OUT)") (class "Default")
      (node (ref "R32") (pin "1") (pinfunction "1_1") (pintype "passive"))
      (node (ref "U$61") (pin "7") (pinfunction "OUT_7") (pintype "output"))
    )
    (net (code "40") (name "Net-(U$62A--IN)") (class "Default")
      (node (ref "R14") (pin "2") (pinfunction "2_2") (pintype "passive"))
      (node (ref "R15") (pin "1") (pinfunction "1_1") (pintype "passive"))
      (node (ref "U$35") (pin "C") (pinfunction "C_C") (pintype "passive"))
      (node (ref "U$62") (pin "2") (pinfunction "-IN_2") (pintype "input"))
    )
    (net (code "41") (name "Net-(U$62A-OUT)") (class "Default")
      (node (ref "U$23") (pin "C") (pinfunction "C_C") (pintype "passive"))
      (node (ref "U$35") (pin "A") (pinfunction "A_A") (pintype "passive"))
      (node (ref "U$62") (pin "1") (pinfunction "OUT_1") (pintype "output"))
    )
    (net (code "42") (name "Net-(U$62B--IN)") (class "Default")
      (node (ref "C4") (pin "1") (pinfunction "1_1") (pintype "passive"))
      (node (ref "R12") (pin "2") (pinfunction "2_2") (pintype "passive"))
      (node (ref "R16") (pin "1") (pinfunction "1_1") (pintype "passive"))
      (node (ref "R19") (pin "1") (pinfunction "1_1") (pintype "passive"))
      (node (ref "U$62") (pin "6") (pinfunction "-IN_6") (pintype "input"))
    )
    (net (code "43") (name "Net-(U$63A-+IN)") (class "Default")
      (node (ref "R13") (pin "2") (pinfunction "2_2") (pintype "passive"))
      (node (ref "R23") (pin "1") (pinfunction "1_1") (pintype "passive"))
      (node (ref "R33") (pin "2") (pinfunction "2_2") (pintype "passive"))
      (node (ref "U$63") (pin "3") (pinfunction "+IN_3") (pintype "input"))
    )
    (net (code "44") (name "Net-(U$63A-OUT)") (class "Default")
      (node (ref "R23") (pin "2") (pinfunction "2_2") (pintype "passive"))
      (node (ref "U$63") (pin "1") (pinfunction "OUT_1") (pintype "output"))
      (node (ref "U$63") (pin "6") (pinfunction "-IN_6") (pintype "input"))
    )
    (net (code "45") (name "Net-(U$63B-+IN)") (class "Default")
      (node (ref "R43") (pin "2") (pinfunction "2_2") (pintype "passive"))
      (node (ref "R44") (pin "2") (pinfunction "2_2") (pintype "passive"))
      (node (ref "U$63") (pin "5") (pinfunction "+IN_5") (pintype "input"))
    )
    (net (code "46") (name "Net-(U$63B-OUT)") (class "Default")
      (node (ref "R25") (pin "1") (pinfunction "1_1") (pintype "passive"))
      (node (ref "U$63") (pin "7") (pinfunction "OUT_7") (pintype "output"))
    )
    (net (code "47") (name "Net-(U$65A-+IN)") (class "Default")
      (node (ref "R5") (pin "2") (pinfunction "2_2") (pintype "passive"))
      (node (ref "R6") (pin "2") (pinfunction "2_2") (pintype "passive"))
      (node (ref "U$65") (pin "3") (pinfunction "+IN_3") (pintype "input"))
    )
    (net (code "48") (name "Net-(U$65A--IN)") (class "Default")
      (node (ref "R39") (pin "2") (pinfunction "2_2") (pintype "passive"))
      (node (ref "R7") (pin "1") (pinfunction "1_1") (pintype "passive"))
      (node (ref "U$65") (pin "4") (pinfunction "-IN_4") (pintype "input"))
    )
    (net (code "49") (name "Net-(U$65A-OUT)") (class "Default")
      (node (ref "R12") (pin "1") (pinfunction "1_1") (pintype "passive"))
      (node (ref "R14") (pin "1") (pinfunction "1_1") (pintype "passive"))
      (node (ref "R7") (pin "2") (pinfunction "2_2") (pintype "passive"))
      (node (ref "U$65") (pin "1") (pinfunction "OUT_1") (pintype "output"))
    )
    (net (code "50") (name "Net-(U$66A-+IN)") (class "Default")
      (node (ref "R41") (pin "1") (pinfunction "1_1") (pintype "passive"))
      (node (ref "U$66") (pin "1") (pinfunction "OUT_1") (pintype "output"))
      (node (ref "U$66") (pin "3") (pinfunction "+IN_3") (pintype "input"))
      (node (ref "U$71") (pin "C") (pinfunction "C_C") (pintype "passive"))
    )
    (net (code "51") (name "Net-(U$67-S)") (class "Default")
      (node (ref "C1") (pin "1") (pinfunction "1_1") (pintype "passive"))
      (node (ref "R1") (pin "2") (pinfunction "2_2") (pintype "passive"))
      (node (ref "R50") (pin "1") (pinfunction "1_1") (pintype "passive"))
      (node (ref "U$67") (pin "2") (pinfunction "S_2") (pintype "passive"))
    )
    (net (code "52") (name "Net-(U$68-S)") (class "Default")
      (node (ref "C2") (pin "1") (pinfunction "1_1") (pintype "passive"))
      (node (ref "R2") (pin "2") (pinfunction "2_2") (pintype "passive"))
      (node (ref "R49") (pin "1") (pinfunction "1_1") (pintype "passive"))
      (node (ref "U$68") (pin "2") (pinfunction "S_2") (pintype "passive"))
    )
    (net (code "53") (name "unconnected-(A/D-Pad17)") (class "Default")
      (node (ref "A/D") (pin "17") (pinfunction "17_17") (pintype "passive"))
    )
    (net (code "54") (name "unconnected-(A/D-Pad19)") (class "Default")
      (node (ref "A/D") (pin "19") (pinfunction "19_19") (pintype "passive"))
    )
    (net (code "55") (name "unconnected-(A/D-Pad21)") (class "Default")
      (node (ref "A/D") (pin "21") (pinfunction "21_21") (pintype "passive"))
    )
    (net (code "56") (name "unconnected-(SV1-Pad2)") (class "Default")
      (node (ref "SV1") (pin "2") (pinfunction "2_2") (pintype "passive"))
    )
  )
)
